# smarttrashcan.net
KiCad netlist of a schematic drawn in Altium Designer
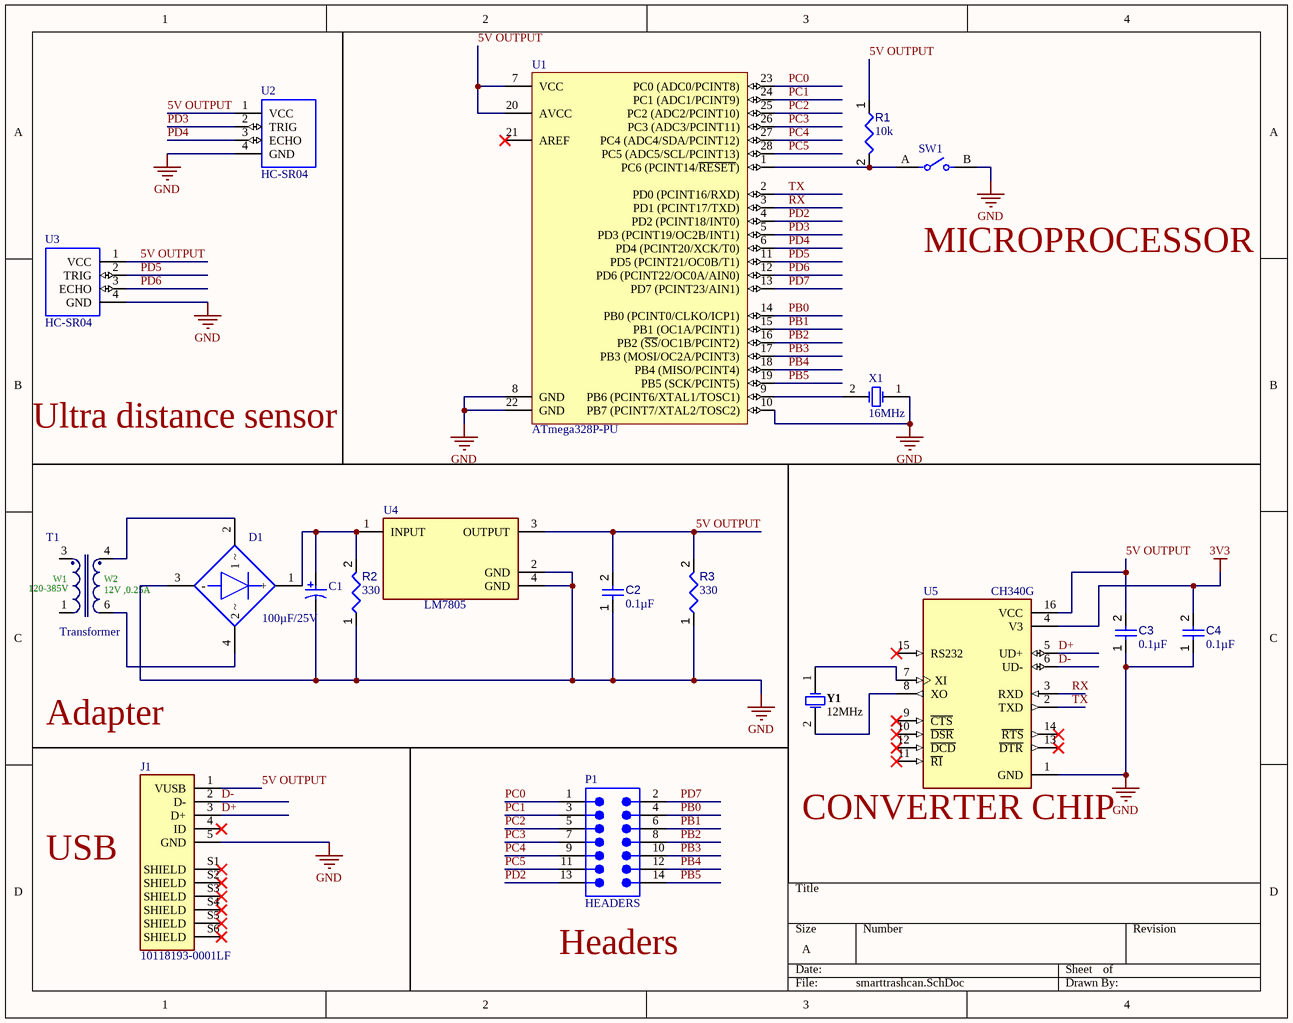
[diagram p0: smarttrashcan.SchDoc]

(export (version "E")
  (design (tool "Eeschema 10.0.6"))
  (components
    (comp (ref "C1")
      (value "100µF/25V")
      (footprint "PNSC-FK-V-D8_V")
      (fields (field (name "MANUFACTURER") "Panasonic"))
      (libsource (lib "Altium Content Vault") (part "CAP-P-2"))
    )
    (comp (ref "C2")
      (value "0.1µF")
      (footprint "CAPC1005X56X25LL10T15")
      (description "Chip Capacitor, 0.1 uF, +/- 5%, 16 V, 0402 (1005 Metric)")
      (fields (field (name "TOLERANCE") "5%") (field (name "Comment") "Capacitor 0.1 uF +/- 5% 16 V 0402"))
      (libsource (lib "Uy Pham") (part "CAP-NP-2"))
    )
    (comp (ref "C3")
      (value "0.1µF")
      (footprint "CAPC1005X56X25LL10T15")
      (description "Chip Capacitor, 0.1 uF, +/- 5%, 16 V, 0402 (1005 Metric)")
      (fields (field (name "TOLERANCE") "5%") (field (name "Comment") "Capacitor 0.1 uF +/- 5% 16 V 0402"))
      (libsource (lib "Uy Pham") (part "CAP-NP-2"))
    )
    (comp (ref "C4")
      (value "0.1µF")
      (footprint "CAPC1005X56X25LL10T15")
      (description "Chip Capacitor, 0.1 uF, +/- 5%, 16 V, 0402 (1005 Metric)")
      (fields (field (name "TOLERANCE") "5%") (field (name "Comment") "Capacitor 0.1 uF +/- 5% 16 V 0402"))
      (libsource (lib "Uy Pham") (part "CAP-NP-2"))
    )
    (comp (ref "D1")
      (value "~")
      (footprint "FP-MBF-MFG")
      (description "Bridge Rectifier Single Phase Standard 1kV Surface Mount MBF")
      (fields (field (name "MANUFACTURER") "Diodes Incorporated"))
      (libsource (lib "Altium Content Vault") (part "c68dd78a3063a12c899a8333093fd1a"))
    )
    (comp (ref "J1")
      (value "10118193-0001LF")
      (footprint "AMPHENOL_10118193-0001LF")
      (description "Right Angle Surface Mount Mount Female USB Connector 100 V ac 1.8A")
      (fields (field (name "MF") "Amphenol ICC"))
      (libsource (lib "Uy Pham") (part "10118193-0001LF"))
    )
    (comp (ref "P1")
      (value "HEADERS")
      (footprint "610114249121")
      (libsource (lib "Altium Content Vault") (part "Header_Male_2R_14P"))
    )
    (comp (ref "R1")
      (value "10k")
      (footprint "RESC0402(1005)_L")
      (description "10K 0.063W 1% 0402 (1005 Metric)  SMD")
      (fields (field (name "POWER") "63mW") (field (name "TOLERANCE") "1%"))
      (libsource (lib "Uy Pham") (part "10KR2F"))
    )
    (comp (ref "R2")
      (value "330")
      (footprint "RESC0402(1005)_L")
      (description "Chip Resistor, 330 Ohms, +/-5 %, 63 mW, -55 to 155 degC, 0402")
      (fields (field (name "POWER") "63mW") (field (name "TOLERANCE") "5%"))
      (libsource (lib "Uy Pham") (part "RES-2"))
    )
    (comp (ref "R3")
      (value "330")
      (footprint "RESC0402(1005)_L")
      (description "Chip Resistor, 330 Ohms, +/-5 %, 63 mW, -55 to 155 degC, 0402")
      (fields (field (name "POWER") "63mW") (field (name "TOLERANCE") "5%"))
      (libsource (lib "Uy Pham") (part "RES-2"))
    )
    (comp (ref "SW1")
      (value "EVQ11Y04K")
      (footprint "FP-EVQ11Y04K-MFG")
      (description "SWITCH TACTILE SPST-NO 0.02A 15V")
      (libsource (lib "Altium Content Vault") (part "2b0b2b19372efd94fa7681498149756"))
    )
    (comp (ref "T1")
      (value "Transformer")
      (footprint "EE13_7_4-Vertical_(EF12.6)")
      (description "Off-Line Transformer WE-UNIT , L=2.8mH")
      (fields (field (name "MANUFACTURER") "Wuerth Elektronik") (field (name "PARTNUMBER") "7491181012"))
      (libsource (lib "Altium Content Vault") (part "WE-7491181012"))
    )
    (comp (ref "U1")
      (value "ATmega328P-PU")
      (footprint "28P3")
      (libsource (lib "Altium Content Vault") (part "MC-8B-ATM48-IL28"))
    )
    (comp (ref "U2")
      (value "HC-SR04")
      (footprint "XCVR_HC-SR04")
      (description "Ultrasonic Sensor Module")
      (libsource (lib "Uy Pham") (part "HC-SR04"))
    )
    (comp (ref "U3")
      (value "HC-SR04")
      (footprint "XCVR_HC-SR04")
      (description "Ultrasonic Sensor Module")
      (libsource (lib "Uy Pham") (part "HC-SR04"))
    )
    (comp (ref "U4")
      (value "LM7805")
      (footprint "FP-DCY0004A-MFG")
      (description "IC REG LINEAR 5V 1.5A SOT223-4")
      (fields
        (field (name "MANUFACTURER PART NUMBER") "LM7805MP/NOPB")
        (field (name "OCTOPART") "https://octopart.com/lm7805mp%2Fnopb-texas+instruments-74629991")
      )
      (libsource (lib "Altium Content Vault") (part "84c6965c160f0d7e9bd6a72b5b454c6"))
    )
    (comp (ref "U5")
      (value "CH340G")
      (footprint "SOIC127P600X180-16N")
      (description "USB Interface Integrated Circuit")
      (fields (field (name "MF") "WCH") (field (name "MP") "Ch340G"))
      (libsource (lib "Uy Pham") (part "CH340G"))
    )
    (comp (ref "X1")
      (value "16MHz")
      (footprint "FOX-FOXSDLF160-20_V")
      (fields (field (name "TOLERANCE") "50ppm") (field (name "MANUFACTURER") "FOX Electronics"))
      (libsource (lib "Uy Pham") (part "XTAL_1-2-2"))
    )
    (comp (ref "Y1")
      (value "12MHz")
      (footprint "FOX-FOXSLF-2_V")
      (description "Resistance Weld Thru-Hole Crystal, 12 MHz, +/-30 ppm, 20 pF, -20 to 70 degC, 2-Pin THD, RoHS, Bulk")
      (fields (field (name "MANUFACTURER") "FOX Electronics") (field (name "TOLERANCE") "50ppm"))
      (libsource (lib "Uy Pham") (part "XTAL-1-2-2"))
    )
  )
  (nets
    (net (code "1") (name "/5V OUTPUT") (class "Default")
      (node (ref "C2") (pin "2") (pinfunction "2_2") (pintype "passive"))
      (node (ref "C3") (pin "2") (pinfunction "2_2") (pintype "passive"))
      (node (ref "J1") (pin "1") (pinfunction "VUSB_1") (pintype "passive"))
      (node (ref "R1") (pin "1") (pinfunction "1_1") (pintype "passive"))
      (node (ref "R3") (pin "2") (pinfunction "2_2") (pintype "passive"))
      (node (ref "U1") (pin "20") (pinfunction "AVCC_20") (pintype "power_in"))
      (node (ref "U1") (pin "7") (pinfunction "VCC_7") (pintype "power_in"))
      (node (ref "U2") (pin "1") (pinfunction "VCC_1") (pintype "power_in"))
      (node (ref "U3") (pin "1") (pinfunction "VCC_1") (pintype "power_in"))
      (node (ref "U4") (pin "3") (pinfunction "OUTPUT_3") (pintype "power_in"))
      (node (ref "U5") (pin "16") (pinfunction "VCC_16") (pintype "power_in"))
    )
    (net (code "2") (name "/D+") (class "Default")
      (node (ref "J1") (pin "3") (pinfunction "D+_3") (pintype "passive"))
      (node (ref "U5") (pin "5") (pinfunction "UD+_5") (pintype "bidirectional"))
    )
    (net (code "3") (name "/D-") (class "Default")
      (node (ref "J1") (pin "2") (pinfunction "D-_2") (pintype "passive"))
      (node (ref "U5") (pin "6") (pinfunction "UD-_6") (pintype "bidirectional"))
    )
    (net (code "4") (name "/PB0") (class "Default")
      (node (ref "P1") (pin "4") (pinfunction "4_4") (pintype "passive"))
      (node (ref "U1") (pin "14") (pinfunction "PB0_(PCINT0/CLKO/ICP1)_14") (pintype "bidirectional"))
    )
    (net (code "5") (name "/PB1") (class "Default")
      (node (ref "P1") (pin "6") (pinfunction "6_6") (pintype "passive"))
      (node (ref "U1") (pin "15") (pinfunction "PB1_(OC1A/PCINT1)_15") (pintype "bidirectional"))
    )
    (net (code "6") (name "/PB2") (class "Default")
      (node (ref "P1") (pin "8") (pinfunction "8_8") (pintype "passive"))
      (node (ref "U1") (pin "16") (pinfunction "PB2_(~{SS}/OC1B/PCINT2)_16") (pintype "bidirectional"))
    )
    (net (code "7") (name "/PB3") (class "Default")
      (node (ref "P1") (pin "10") (pinfunction "10_10") (pintype "passive"))
      (node (ref "U1") (pin "17") (pinfunction "PB3_(MOSI/OC2A/PCINT3)_17") (pintype "bidirectional"))
    )
    (net (code "8") (name "/PB4") (class "Default")
      (node (ref "P1") (pin "12") (pinfunction "12_12") (pintype "passive"))
      (node (ref "U1") (pin "18") (pinfunction "PB4_(MISO/PCINT4)_18") (pintype "bidirectional"))
    )
    (net (code "9") (name "/PB5") (class "Default")
      (node (ref "P1") (pin "14") (pinfunction "14_14") (pintype "passive"))
      (node (ref "U1") (pin "19") (pinfunction "PB5_(SCK/PCINT5)_19") (pintype "bidirectional"))
    )
    (net (code "10") (name "/PC0") (class "Default")
      (node (ref "P1") (pin "1") (pinfunction "1_1") (pintype "passive"))
      (node (ref "U1") (pin "23") (pinfunction "PC0_(ADC0/PCINT8)_23") (pintype "bidirectional"))
    )
    (net (code "11") (name "/PC1") (class "Default")
      (node (ref "P1") (pin "3") (pinfunction "3_3") (pintype "passive"))
      (node (ref "U1") (pin "24") (pinfunction "PC1_(ADC1/PCINT9)_24") (pintype "bidirectional"))
    )
    (net (code "12") (name "/PC2") (class "Default")
      (node (ref "P1") (pin "5") (pinfunction "5_5") (pintype "passive"))
      (node (ref "U1") (pin "25") (pinfunction "PC2_(ADC2/PCINT10)_25") (pintype "bidirectional"))
    )
    (net (code "13") (name "/PC3") (class "Default")
      (node (ref "P1") (pin "7") (pinfunction "7_7") (pintype "passive"))
      (node (ref "U1") (pin "26") (pinfunction "PC3_(ADC3/PCINT11)_26") (pintype "bidirectional"))
    )
    (net (code "14") (name "/PC4") (class "Default")
      (node (ref "P1") (pin "9") (pinfunction "9_9") (pintype "passive"))
      (node (ref "U1") (pin "27") (pinfunction "PC4_(ADC4/SDA/PCINT12)_27") (pintype "bidirectional"))
    )
    (net (code "15") (name "/PC5") (class "Default")
      (node (ref "P1") (pin "11") (pinfunction "11_11") (pintype "passive"))
      (node (ref "U1") (pin "28") (pinfunction "PC5_(ADC5/SCL/PCINT13)_28") (pintype "bidirectional"))
    )
    (net (code "16") (name "/PD2") (class "Default")
      (node (ref "P1") (pin "13") (pinfunction "13_13") (pintype "passive"))
      (node (ref "U1") (pin "4") (pinfunction "PD2_(PCINT18/INT0)_4") (pintype "bidirectional"))
    )
    (net (code "17") (name "/PD3") (class "Default")
      (node (ref "U1") (pin "5") (pinfunction "PD3_(PCINT19/OC2B/INT1)_5") (pintype "bidirectional"))
      (node (ref "U2") (pin "2") (pinfunction "TRIG_2") (pintype "bidirectional"))
    )
    (net (code "18") (name "/PD4") (class "Default")
      (node (ref "U1") (pin "6") (pinfunction "PD4_(PCINT20/XCK/T0)_6") (pintype "bidirectional"))
      (node (ref "U2") (pin "3") (pinfunction "ECHO_3") (pintype "bidirectional"))
    )
    (net (code "19") (name "/PD5") (class "Default")
      (node (ref "U1") (pin "11") (pinfunction "PD5_(PCINT21/OC0B/T1)_11") (pintype "bidirectional"))
      (node (ref "U3") (pin "2") (pinfunction "TRIG_2") (pintype "bidirectional"))
    )
    (net (code "20") (name "/PD6") (class "Default")
      (node (ref "U1") (pin "12") (pinfunction "PD6_(PCINT22/OC0A/AIN0)_12") (pintype "bidirectional"))
      (node (ref "U3") (pin "3") (pinfunction "ECHO_3") (pintype "bidirectional"))
    )
    (net (code "21") (name "/PD7") (class "Default")
      (node (ref "P1") (pin "2") (pinfunction "2_2") (pintype "passive"))
      (node (ref "U1") (pin "13") (pinfunction "PD7_(PCINT23/AIN1)_13") (pintype "bidirectional"))
    )
    (net (code "22") (name "/RX") (class "Default")
      (node (ref "U1") (pin "3") (pinfunction "PD1_(PCINT17/TXD)_3") (pintype "bidirectional"))
      (node (ref "U5") (pin "3") (pinfunction "RXD_3") (pintype "input"))
    )
    (net (code "23") (name "/TX") (class "Default")
      (node (ref "U1") (pin "2") (pinfunction "PD0_(PCINT16/RXD)_2") (pintype "bidirectional"))
      (node (ref "U5") (pin "2") (pinfunction "TXD_2") (pintype "output"))
    )
    (net (code "24") (name "3V3") (class "Default")
      (node (ref "C4") (pin "2") (pinfunction "2_2") (pintype "passive"))
      (node (ref "U5") (pin "4") (pinfunction "V3_4") (pintype "power_in"))
    )
    (net (code "25") (name "GND") (class "Default")
      (node (ref "C1") (pin "2") (pinfunction "2_2") (pintype "passive"))
      (node (ref "C2") (pin "1") (pinfunction "1_1") (pintype "passive"))
      (node (ref "C3") (pin "1") (pinfunction "1_1") (pintype "passive"))
      (node (ref "C4") (pin "1") (pinfunction "1_1") (pintype "passive"))
      (node (ref "D1") (pin "3") (pinfunction "-_3") (pintype "passive"))
      (node (ref "J1") (pin "5") (pinfunction "GND_5") (pintype "passive"))
      (node (ref "R2") (pin "1") (pinfunction "1_1") (pintype "passive"))
      (node (ref "R3") (pin "1") (pinfunction "1_1") (pintype "passive"))
      (node (ref "SW1") (pin "B") (pinfunction "B_B") (pintype "passive"))
      (node (ref "U1") (pin "10") (pinfunction "PB7_(PCINT7/XTAL2/TOSC2)_10") (pintype "bidirectional"))
      (node (ref "U1") (pin "22") (pinfunction "GND_22") (pintype "power_in"))
      (node (ref "U1") (pin "8") (pinfunction "GND_8") (pintype "power_in"))
      (node (ref "U2") (pin "4") (pinfunction "GND_4") (pintype "power_in"))
      (node (ref "U3") (pin "4") (pinfunction "GND_4") (pintype "power_in"))
      (node (ref "U4") (pin "2") (pinfunction "GND_2") (pintype "power_in"))
      (node (ref "U4") (pin "4") (pinfunction "GND_4") (pintype "power_in"))
      (node (ref "U5") (pin "1") (pinfunction "GND_1") (pintype "power_in"))
      (node (ref "X1") (pin "1") (pinfunction "X1_1") (pintype "passive"))
    )
    (net (code "26") (name "Net-(D1-+)") (class "Default")
      (node (ref "C1") (pin "1") (pinfunction "1_1") (pintype "passive"))
      (node (ref "D1") (pin "1") (pinfunction "+_1") (pintype "passive"))
      (node (ref "R2") (pin "2") (pinfunction "2_2") (pintype "passive"))
      (node (ref "U4") (pin "1") (pinfunction "INPUT_1") (pintype "power_in"))
    )
    (net (code "27") (name "Net-(D1-1_~)") (class "Default")
      (node (ref "D1") (pin "2") (pinfunction "1_~_2") (pintype "passive"))
      (node (ref "T1") (pin "4") (pinfunction "4_4") (pintype "passive"))
    )
    (net (code "28") (name "Net-(D1-2_~)") (class "Default")
      (node (ref "D1") (pin "4") (pinfunction "2_~_4") (pintype "passive"))
      (node (ref "T1") (pin "6") (pinfunction "6_6") (pintype "passive"))
    )
    (net (code "29") (name "Net-(U1-PB6_(PCINT6{slash}XTAL1{slash}TOSC1))") (class "Default")
      (node (ref "U1") (pin "9") (pinfunction "PB6_(PCINT6/XTAL1/TOSC1)_9") (pintype "bidirectional"))
      (node (ref "X1") (pin "2") (pinfunction "X2_2") (pintype "passive"))
    )
    (net (code "30") (name "Net-(U1-PC6_(PCINT14{slash}~{RESET}))") (class "Default")
      (node (ref "R1") (pin "2") (pinfunction "2_2") (pintype "passive"))
      (node (ref "SW1") (pin "A") (pinfunction "A_A") (pintype "passive"))
      (node (ref "U1") (pin "1") (pinfunction "PC6_(PCINT14/~{RESET})_1") (pintype "bidirectional"))
    )
    (net (code "31") (name "Net-(U5-XI)") (class "Default")
      (node (ref "U5") (pin "7") (pinfunction "XI_7") (pintype "input"))
      (node (ref "Y1") (pin "1") (pinfunction "1_1") (pintype "passive"))
    )
    (net (code "32") (name "Net-(U5-XO)") (class "Default")
      (node (ref "U5") (pin "8") (pinfunction "XO_8") (pintype "output"))
      (node (ref "Y1") (pin "2") (pinfunction "2_2") (pintype "passive"))
    )
    (net (code "33") (name "unconnected-(J1-ID-Pad4)") (class "Default")
      (node (ref "J1") (pin "4") (pinfunction "ID_4") (pintype "passive+no_connect"))
    )
    (net (code "34") (name "unconnected-(J1-SHIELD-PadS1)") (class "Default")
      (node (ref "J1") (pin "S1") (pinfunction "SHIELD_S1") (pintype "passive+no_connect"))
    )
    (net (code "35") (name "unconnected-(J1-SHIELD-PadS2)") (class "Default")
      (node (ref "J1") (pin "S2") (pinfunction "SHIELD_S2") (pintype "passive+no_connect"))
    )
    (net (code "36") (name "unconnected-(J1-SHIELD-PadS3)") (class "Default")
      (node (ref "J1") (pin "S3") (pinfunction "SHIELD_S3") (pintype "passive+no_connect"))
    )
    (net (code "37") (name "unconnected-(J1-SHIELD-PadS4)") (class "Default")
      (node (ref "J1") (pin "S4") (pinfunction "SHIELD_S4") (pintype "passive+no_connect"))
    )
    (net (code "38") (name "unconnected-(J1-SHIELD-PadS5)") (class "Default")
      (node (ref "J1") (pin "S5") (pinfunction "SHIELD_S5") (pintype "passive+no_connect"))
    )
    (net (code "39") (name "unconnected-(J1-SHIELD-PadS6)") (class "Default")
      (node (ref "J1") (pin "S6") (pinfunction "SHIELD_S6") (pintype "passive+no_connect"))
    )
    (net (code "40") (name "unconnected-(T1-Pad1)") (class "Default")
      (node (ref "T1") (pin "1") (pinfunction "1_1") (pintype "passive"))
    )
    (net (code "41") (name "unconnected-(T1-Pad3)") (class "Default")
      (node (ref "T1") (pin "3") (pinfunction "3_3") (pintype "passive"))
    )
    (net (code "42") (name "unconnected-(U1-AREF-Pad21)") (class "Default")
      (node (ref "U1") (pin "21") (pinfunction "AREF_21") (pintype "power_in+no_connect"))
    )
    (net (code "43") (name "unconnected-(U5-RS232-Pad15)") (class "Default")
      (node (ref "U5") (pin "15") (pinfunction "RS232_15") (pintype "input+no_connect"))
    )
    (net (code "44") (name "unconnected-(U5-~{CTS}-Pad9)") (class "Default")
      (node (ref "U5") (pin "9") (pinfunction "~{CTS}_9") (pintype "input+no_connect"))
    )
    (net (code "45") (name "unconnected-(U5-~{DCD}-Pad12)") (class "Default")
      (node (ref "U5") (pin "12") (pinfunction "~{DCD}_12") (pintype "input+no_connect"))
    )
    (net (code "46") (name "unconnected-(U5-~{DSR}-Pad10)") (class "Default")
      (node (ref "U5") (pin "10") (pinfunction "~{DSR}_10") (pintype "input+no_connect"))
    )
    (net (code "47") (name "unconnected-(U5-~{DTR}-Pad13)") (class "Default")
      (node (ref "U5") (pin "13") (pinfunction "~{DTR}_13") (pintype "output+no_connect"))
    )
    (net (code "48") (name "unconnected-(U5-~{RI}-Pad11)") (class "Default")
      (node (ref "U5") (pin "11") (pinfunction "~{RI}_11") (pintype "input+no_connect"))
    )
    (net (code "49") (name "unconnected-(U5-~{RTS}-Pad14)") (class "Default")
      (node (ref "U5") (pin "14") (pinfunction "~{RTS}_14") (pintype "output+no_connect"))
    )
  )
)
